# SensorThing.net
KiCad netlist of a schematic drawn in EAGLE
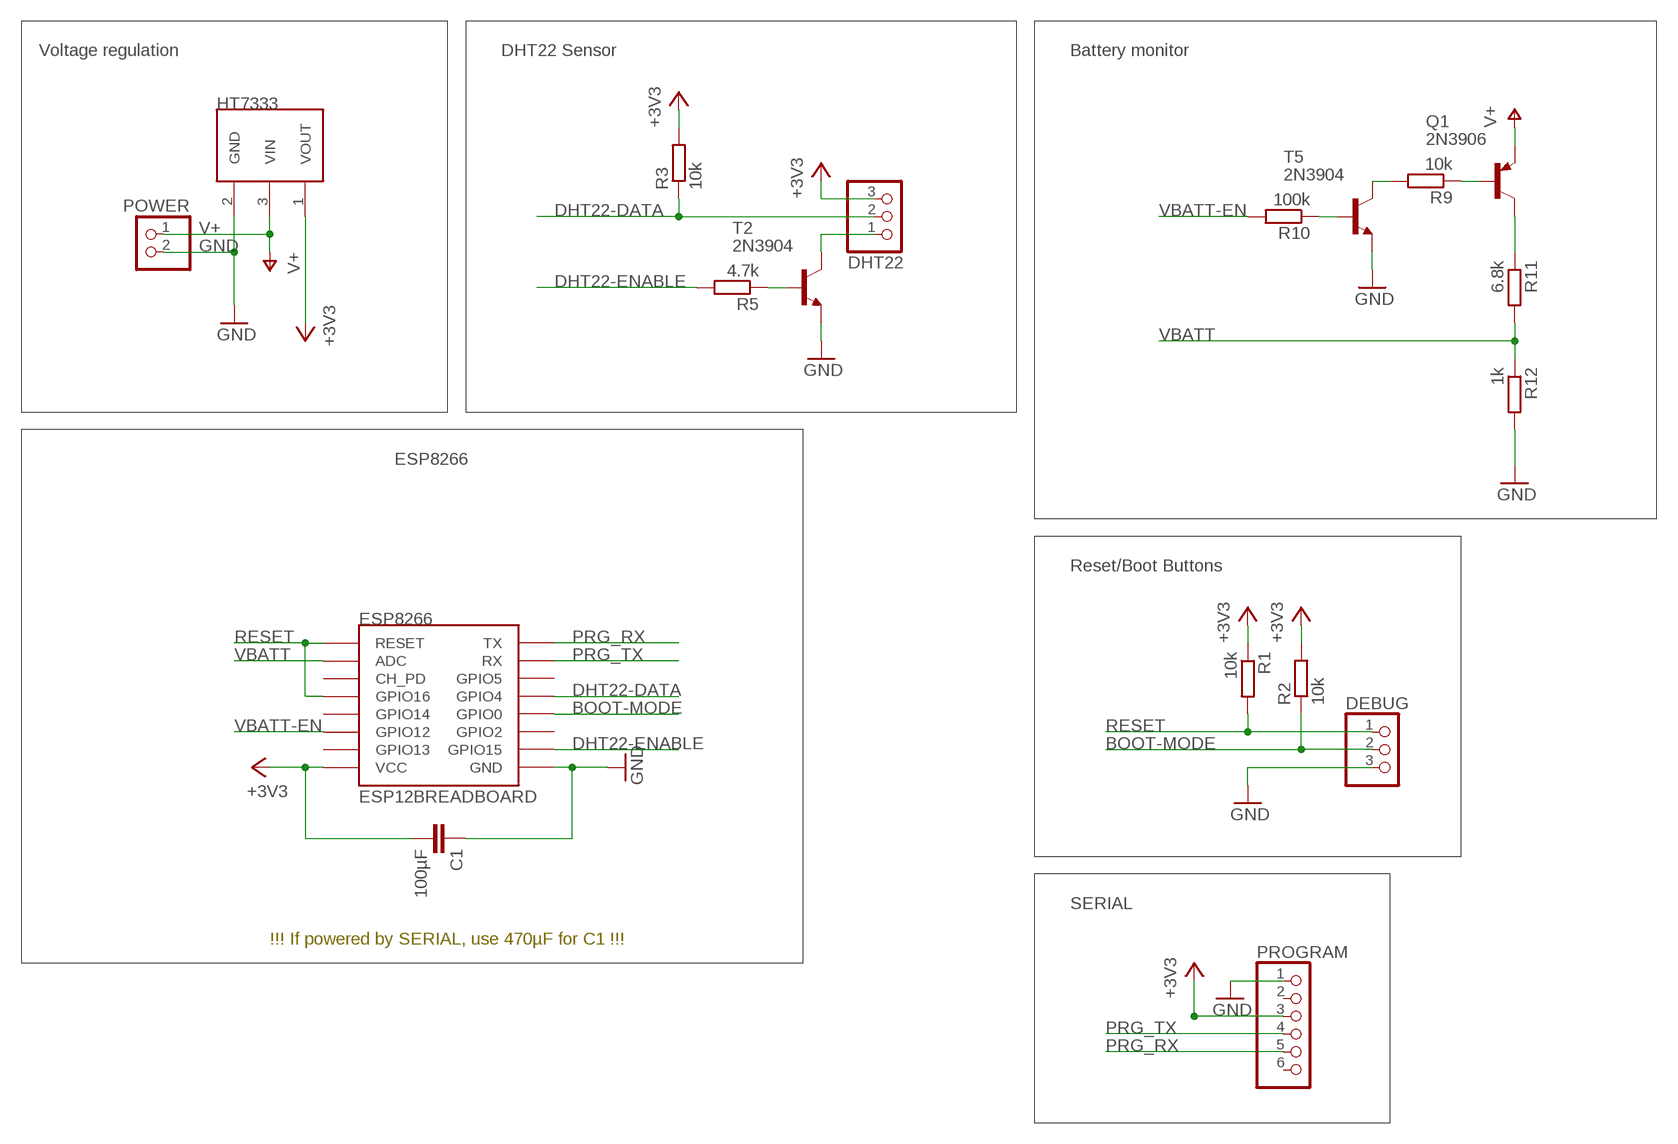
[diagram p0: schematic, sheet 1]

(export (version "E")
  (design (tool "Eeschema 10.0.6"))
  (components
    (comp (ref "C1")
      (value "100µF")
      (footprint "eagle-import:C025-024X044")
      (libsource (lib "eagle-import") (part "C-EU025-024X044"))
    )
    (comp (ref "DEBUG")
      (value "PINHD-1X3/90")
      (footprint "eagle-import:1X03_90")
      (libsource (lib "eagle-import") (part "PINHD-1X3/90"))
    )
    (comp (ref "DHT22")
      (value "PINHD-1X3/90")
      (footprint "eagle-import:1X03_90")
      (libsource (lib "eagle-import") (part "PINHD-1X3/90"))
    )
    (comp (ref "ESP8266")
      (value "ESP12BREADBOARD")
      (footprint "eagle-import:ESP12E-BREADBOARD")
      (libsource (lib "eagle-import") (part "ESP12BREADBOARD"))
    )
    (comp (ref "HT7333")
      (value "HT73XX")
      (footprint "eagle-import:SOT89-R")
      (libsource (lib "eagle-import") (part "HT73XX"))
    )
    (comp (ref "POWER")
      (value "PINHD-1X2/90")
      (footprint "eagle-import:1X02_90")
      (libsource (lib "eagle-import") (part "PINHD-1X2/90"))
    )
    (comp (ref "PROGRAM")
      (value "PINHD-1X6/90")
      (footprint "eagle-import:1X06_90")
      (libsource (lib "eagle-import") (part "PINHD-1X6/90"))
    )
    (comp (ref "Q1")
      (value "2N3906")
      (footprint "eagle-import:TO92")
      (libsource (lib "eagle-import") (part "2N3906"))
    )
    (comp (ref "R1")
      (value "10k")
      (footprint "eagle-import:0204_7")
      (libsource (lib "eagle-import") (part "R-EU_0204/7"))
    )
    (comp (ref "R2")
      (value "10k")
      (footprint "eagle-import:0204_7")
      (libsource (lib "eagle-import") (part "R-EU_0204/7"))
    )
    (comp (ref "R3")
      (value "10k")
      (footprint "eagle-import:0204_7")
      (libsource (lib "eagle-import") (part "R-EU_0204/7"))
    )
    (comp (ref "R5")
      (value "4.7k")
      (footprint "eagle-import:M0805")
      (libsource (lib "eagle-import") (part "R-EU_M0805"))
    )
    (comp (ref "R9")
      (value "10k")
      (footprint "eagle-import:0204_7")
      (libsource (lib "eagle-import") (part "R-EU_0204/7"))
    )
    (comp (ref "R10")
      (value "100k")
      (footprint "eagle-import:M0805")
      (libsource (lib "eagle-import") (part "R-EU_M0805"))
    )
    (comp (ref "R11")
      (value "6.8k")
      (footprint "eagle-import:0204_7")
      (libsource (lib "eagle-import") (part "R-EU_0204/7"))
    )
    (comp (ref "R12")
      (value "1k")
      (footprint "eagle-import:M0805")
      (libsource (lib "eagle-import") (part "R-EU_M0805"))
    )
    (comp (ref "T2")
      (value "2N3904")
      (footprint "eagle-import:TO92")
      (libsource (lib "eagle-import") (part "2N3904"))
    )
    (comp (ref "T5")
      (value "2N3904")
      (footprint "eagle-import:TO92")
      (libsource (lib "eagle-import") (part "2N3904"))
    )
  )
  (nets
    (net (code "1") (name "+3V3") (class "Default")
      (node (ref "C1") (pin "2") (pinfunction "2_2") (pintype "passive"))
      (node (ref "DHT22") (pin "3") (pinfunction "3_3") (pintype "passive"))
      (node (ref "ESP8266") (pin "8") (pinfunction "VCC_8") (pintype "bidirectional"))
      (node (ref "HT7333") (pin "1") (pinfunction "VOUT_1") (pintype "bidirectional"))
      (node (ref "PROGRAM") (pin "3") (pinfunction "3_3") (pintype "passive"))
      (node (ref "R1") (pin "1") (pinfunction "1_1") (pintype "passive"))
      (node (ref "R2") (pin "2") (pinfunction "2_2") (pintype "passive"))
      (node (ref "R3") (pin "2") (pinfunction "2_2") (pintype "passive"))
    )
    (net (code "2") (name "/BOOT-MODE") (class "Default")
      (node (ref "DEBUG") (pin "2") (pinfunction "2_2") (pintype "passive"))
      (node (ref "ESP8266") (pin "12") (pinfunction "GPIO0_12") (pintype "bidirectional"))
      (node (ref "R2") (pin "1") (pinfunction "1_1") (pintype "passive"))
    )
    (net (code "3") (name "/DHT22-DATA") (class "Default")
      (node (ref "DHT22") (pin "2") (pinfunction "2_2") (pintype "passive"))
      (node (ref "ESP8266") (pin "13") (pinfunction "GPIO4_13") (pintype "bidirectional"))
      (node (ref "R3") (pin "1") (pinfunction "1_1") (pintype "passive"))
    )
    (net (code "4") (name "/DHT22-ENABLE") (class "Default")
      (node (ref "ESP8266") (pin "10") (pinfunction "GPIO15_10") (pintype "bidirectional"))
      (node (ref "R5") (pin "2") (pinfunction "2_2") (pintype "passive"))
    )
    (net (code "5") (name "/PRG_RX") (class "Default")
      (node (ref "ESP8266") (pin "16") (pinfunction "TX_16") (pintype "bidirectional"))
      (node (ref "PROGRAM") (pin "5") (pinfunction "5_5") (pintype "passive"))
    )
    (net (code "6") (name "/PRG_TX") (class "Default")
      (node (ref "ESP8266") (pin "15") (pinfunction "RX_15") (pintype "bidirectional"))
      (node (ref "PROGRAM") (pin "4") (pinfunction "4_4") (pintype "passive"))
    )
    (net (code "7") (name "/RESET") (class "Default")
      (node (ref "DEBUG") (pin "1") (pinfunction "1_1") (pintype "passive"))
      (node (ref "ESP8266") (pin "1") (pinfunction "RESET_1") (pintype "bidirectional"))
      (node (ref "ESP8266") (pin "4") (pinfunction "GPIO16_4") (pintype "bidirectional"))
      (node (ref "R1") (pin "2") (pinfunction "2_2") (pintype "passive"))
    )
    (net (code "8") (name "/VBATT") (class "Default")
      (node (ref "ESP8266") (pin "2") (pinfunction "ADC_2") (pintype "bidirectional"))
      (node (ref "R11") (pin "2") (pinfunction "2_2") (pintype "passive"))
      (node (ref "R12") (pin "1") (pinfunction "1_1") (pintype "passive"))
    )
    (net (code "9") (name "/VBATT-EN") (class "Default")
      (node (ref "ESP8266") (pin "6") (pinfunction "GPIO12_6") (pintype "bidirectional"))
      (node (ref "R10") (pin "2") (pinfunction "2_2") (pintype "passive"))
    )
    (net (code "10") (name "GND") (class "Default")
      (node (ref "C1") (pin "1") (pinfunction "1_1") (pintype "passive"))
      (node (ref "DEBUG") (pin "3") (pinfunction "3_3") (pintype "passive"))
      (node (ref "ESP8266") (pin "9") (pinfunction "GND_9") (pintype "bidirectional"))
      (node (ref "HT7333") (pin "2") (pinfunction "GND_2") (pintype "bidirectional"))
      (node (ref "POWER") (pin "2") (pinfunction "2_2") (pintype "passive"))
      (node (ref "PROGRAM") (pin "1") (pinfunction "1_1") (pintype "passive"))
      (node (ref "R12") (pin "2") (pinfunction "2_2") (pintype "passive"))
      (node (ref "T2") (pin "3") (pinfunction "E_3") (pintype "passive"))
      (node (ref "T5") (pin "3") (pinfunction "E_3") (pintype "passive"))
    )
    (net (code "11") (name "Net-(Q1-B)") (class "Default")
      (node (ref "Q1") (pin "2") (pinfunction "B_2") (pintype "passive"))
      (node (ref "R9") (pin "1") (pinfunction "1_1") (pintype "passive"))
    )
    (net (code "12") (name "Net-(Q1-C)") (class "Default")
      (node (ref "Q1") (pin "1") (pinfunction "C_1") (pintype "passive"))
      (node (ref "R11") (pin "1") (pinfunction "1_1") (pintype "passive"))
    )
    (net (code "13") (name "Net-(T2-B)") (class "Default")
      (node (ref "R5") (pin "1") (pinfunction "1_1") (pintype "passive"))
      (node (ref "T2") (pin "2") (pinfunction "B_2") (pintype "passive"))
    )
    (net (code "14") (name "Net-(T2-C)") (class "Default")
      (node (ref "DHT22") (pin "1") (pinfunction "1_1") (pintype "passive"))
      (node (ref "T2") (pin "1") (pinfunction "C_1") (pintype "passive"))
    )
    (net (code "15") (name "Net-(T5-B)") (class "Default")
      (node (ref "R10") (pin "1") (pinfunction "1_1") (pintype "passive"))
      (node (ref "T5") (pin "2") (pinfunction "B_2") (pintype "passive"))
    )
    (net (code "16") (name "Net-(T5-C)") (class "Default")
      (node (ref "R9") (pin "2") (pinfunction "2_2") (pintype "passive"))
      (node (ref "T5") (pin "1") (pinfunction "C_1") (pintype "passive"))
    )
    (net (code "17") (name "V+") (class "Default")
      (node (ref "HT7333") (pin "3") (pinfunction "VIN_3") (pintype "bidirectional"))
      (node (ref "POWER") (pin "1") (pinfunction "1_1") (pintype "passive"))
      (node (ref "Q1") (pin "3") (pinfunction "E_3") (pintype "passive"))
    )
    (net (code "18") (name "unconnected-(ESP8266-CH_PD-Pad3)") (class "Default")
      (node (ref "ESP8266") (pin "3") (pinfunction "CH_PD_3") (pintype "bidirectional"))
    )
    (net (code "19") (name "unconnected-(ESP8266-GPIO2-Pad11)") (class "Default")
      (node (ref "ESP8266") (pin "11") (pinfunction "GPIO2_11") (pintype "bidirectional"))
    )
    (net (code "20") (name "unconnected-(ESP8266-GPIO5-Pad14)") (class "Default")
      (node (ref "ESP8266") (pin "14") (pinfunction "GPIO5_14") (pintype "bidirectional"))
    )
    (net (code "21") (name "unconnected-(ESP8266-GPIO13-Pad7)") (class "Default")
      (node (ref "ESP8266") (pin "7") (pinfunction "GPIO13_7") (pintype "bidirectional"))
    )
    (net (code "22") (name "unconnected-(ESP8266-GPIO14-Pad5)") (class "Default")
      (node (ref "ESP8266") (pin "5") (pinfunction "GPIO14_5") (pintype "bidirectional"))
    )
    (net (code "23") (name "unconnected-(PROGRAM-Pad2)") (class "Default")
      (node (ref "PROGRAM") (pin "2") (pinfunction "2_2") (pintype "passive"))
    )
    (net (code "24") (name "unconnected-(PROGRAM-Pad6)") (class "Default")
      (node (ref "PROGRAM") (pin "6") (pinfunction "6_6") (pintype "passive"))
    )
  )
)
